# Power.net
KiCad netlist of a schematic drawn in Altium Designer
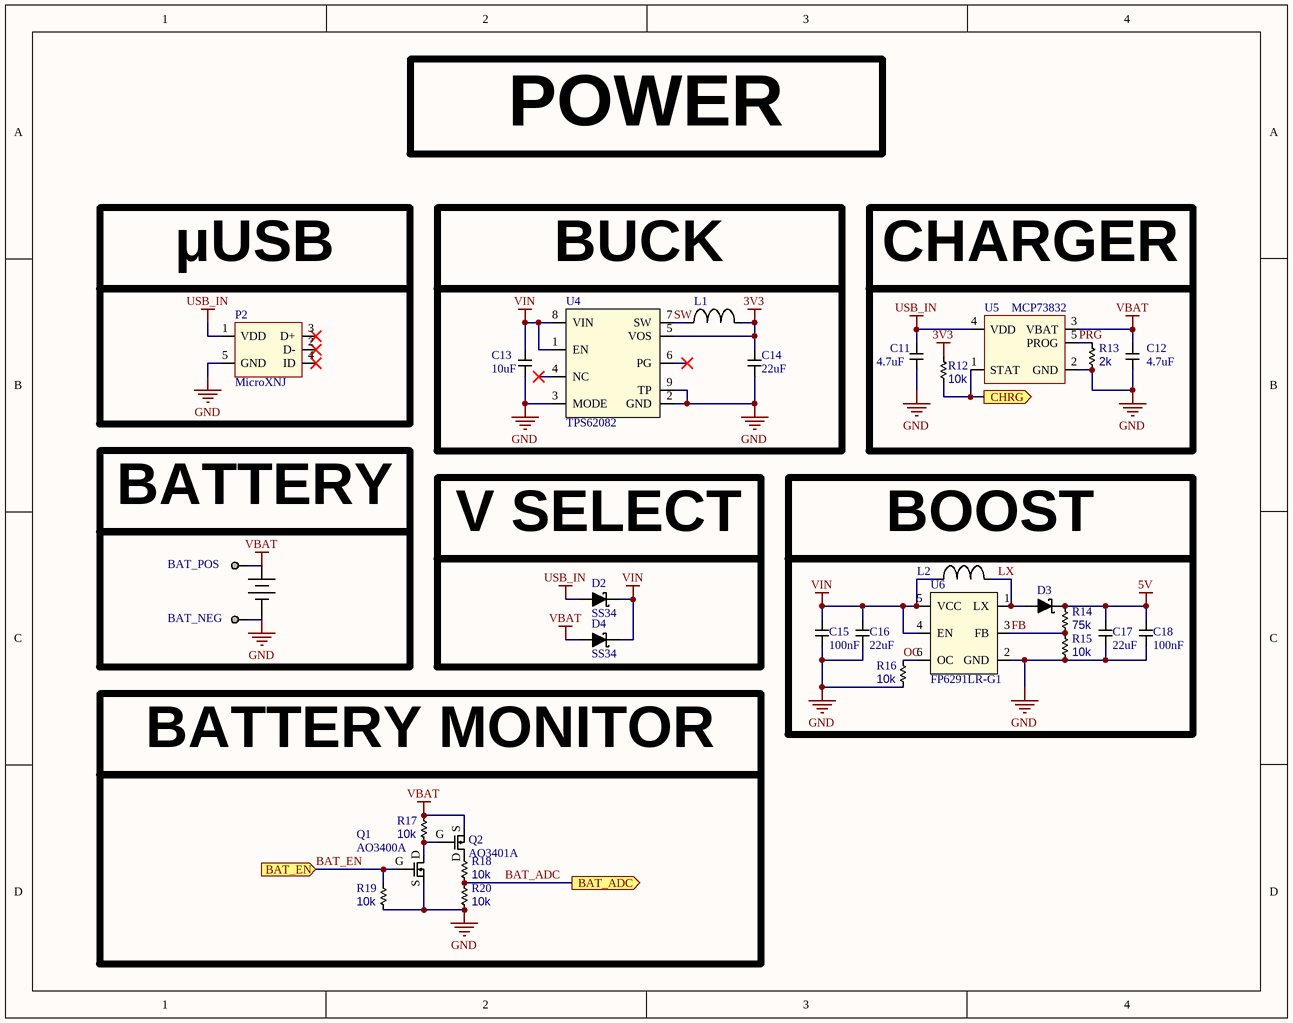
[diagram p0: Power.SchDoc]

(export (version "E")
  (design (tool "Eeschema 10.0.6"))
  (components
    (comp (ref "BAT_NEG")
      (value "18 AWG Hole")
      (footprint "18 AWG Hole")
      (libsource (lib "smLib") (part "18 AWG Hole"))
    )
    (comp (ref "BAT_POS")
      (value "18 AWG Hole")
      (footprint "18 AWG Hole")
      (libsource (lib "smLib") (part "18 AWG Hole"))
    )
    (comp (ref "C11")
      (value "4.7uF")
      (footprint "CAP_0402_HIGH")
      (description "0402 Capacitor")
      (libsource (lib "smLib") (part "Capacitor_0402"))
    )
    (comp (ref "C12")
      (value "4.7uF")
      (footprint "CAP_0402_HIGH")
      (description "0402 Capacitor")
      (libsource (lib "smLib") (part "Capacitor_0402"))
    )
    (comp (ref "C13")
      (value "10uF")
      (footprint "CAP_0603_HIGH")
      (description "0603 Capacitor")
      (libsource (lib "smLib") (part "Capacitor_0603"))
    )
    (comp (ref "C14")
      (value "22uF")
      (footprint "CAP_0603_HIGH")
      (description "0603 Capacitor")
      (libsource (lib "smLib") (part "Capacitor_0603"))
    )
    (comp (ref "C15")
      (value "100nF")
      (footprint "CAP_0402_HIGH")
      (description "0402 Capacitor")
      (libsource (lib "smLib") (part "Capacitor_0402"))
    )
    (comp (ref "C16")
      (value "22uF")
      (footprint "CAP_0603_HIGH")
      (description "0603 Capacitor")
      (libsource (lib "smLib") (part "Capacitor_0603"))
    )
    (comp (ref "C17")
      (value "22uF")
      (footprint "CAP_0603_HIGH")
      (description "0603 Capacitor")
      (libsource (lib "smLib") (part "Capacitor_0603"))
    )
    (comp (ref "C18")
      (value "100nF")
      (footprint "CAP_0402_HIGH")
      (description "0402 Capacitor")
      (libsource (lib "smLib") (part "Capacitor_0402"))
    )
    (comp (ref "D2")
      (value "SS34")
      (footprint "SS34")
      (description "SS34 40V 3A 550mV @ 3A SMA(DO-214AC) Schottky Barrier Diodes (SBD) ROHS")
      (libsource (lib "smLib") (part "SS34"))
    )
    (comp (ref "D3")
      (value "SS34")
      (footprint "SS34")
      (description "SS34 40V 3A 550mV @ 3A SMA(DO-214AC) Schottky Barrier Diodes (SBD) ROHS")
      (libsource (lib "smLib") (part "SS34"))
    )
    (comp (ref "D4")
      (value "SS34")
      (footprint "SS34")
      (description "SS34 40V 3A 550mV @ 3A SMA(DO-214AC) Schottky Barrier Diodes (SBD) ROHS")
      (libsource (lib "smLib") (part "SS34"))
    )
    (comp (ref "L1")
      (value "YNR3015-2R2M")
      (footprint "YNR3015-2R2M")
      (description "YNR3015-2R2M 2.2uH ±20% 1.6A 30mΩ SMD,3.0x3.0x1.5mm Power Inductors RoHS")
      (libsource (lib "smLib") (part "YNR3015-2R2M"))
    )
    (comp (ref "L2")
      (value "VLS3015ET-3R3M")
      (footprint "VLS3015ET-3R3M")
      (description "VLS3015ET-3R3M 3.3 µH Shielded Wirewound Inductor 1.15 A 112mOhm Max Nonstandard")
      (libsource (lib "smLib") (part "VLS3015ET-3R3M"))
    )
    (comp (ref "P2") (value "MicroXNJ") (footprint "MicroXNJ") (libsource (lib "smLib") (part "MicroXNJ")))
    (comp (ref "Q1")
      (value "AO3400A")
      (footprint "AO3400A")
      (description "AO3400A N-Channel 30 V 5.7A (Ta) 1.4W (Ta) Surface Mount SOT-23-3")
      (libsource (lib "smLib") (part "AO3400A"))
    )
    (comp (ref "Q2")
      (value "AO3401A")
      (footprint "AO3401A")
      (description "AO3401A MOSFET P-CH 30V 4A SOT23")
      (libsource (lib "smLib") (part "AO3401A"))
    )
    (comp (ref "R12")
      (value "10k")
      (footprint "RES_0402_HIGH")
      (description "0402 Resistor")
      (libsource (lib "smLib") (part "Resistor_0402"))
    )
    (comp (ref "R13")
      (value "2k")
      (footprint "RES_0402_HIGH")
      (description "0402 Resistor")
      (libsource (lib "smLib") (part "Resistor_0402"))
    )
    (comp (ref "R14")
      (value "75k")
      (footprint "RES_0402_HIGH")
      (description "0402 Resistor")
      (libsource (lib "smLib") (part "Resistor_0402"))
    )
    (comp (ref "R15")
      (value "10k")
      (footprint "RES_0402_HIGH")
      (description "0402 Resistor")
      (libsource (lib "smLib") (part "Resistor_0402"))
    )
    (comp (ref "R16")
      (value "10k")
      (footprint "RES_0402_HIGH")
      (description "0402 Resistor")
      (libsource (lib "smLib") (part "Resistor_0402"))
    )
    (comp (ref "R17")
      (value "10k")
      (footprint "RES_0402_HIGH")
      (description "0402 Resistor")
      (libsource (lib "smLib") (part "Resistor_0402"))
    )
    (comp (ref "R18")
      (value "10k")
      (footprint "RES_0402_HIGH")
      (description "0402 Resistor")
      (libsource (lib "smLib") (part "Resistor_0402"))
    )
    (comp (ref "R19")
      (value "10k")
      (footprint "RES_0402_HIGH")
      (description "0402 Resistor")
      (libsource (lib "smLib") (part "Resistor_0402"))
    )
    (comp (ref "R20")
      (value "10k")
      (footprint "RES_0402_HIGH")
      (description "0402 Resistor")
      (libsource (lib "smLib") (part "Resistor_0402"))
    )
    (comp (ref "U4")
      (value "TPS62082")
      (footprint "TPS62082")
      (description "TPS62082 Buck Switching Regulator IC Positive Fixed 3.3V 1 Output 1.2A 8-WFDFN Exposed Pad")
      (libsource (lib "smLib") (part "TPS62082"))
    )
    (comp (ref "U5")
      (value "MCP73832")
      (footprint "MCP73831")
      (description "MCP73831 Charger IC Lithium-Ion/Polymer")
      (libsource (lib "smLib") (part "MCP73831"))
    )
    (comp (ref "U6")
      (value "FP6291LR-G1")
      (footprint "FP6291LR-G1")
      (description "FP6291LR-G1 2A 5.5V SOT-23-6 DC-DC Converters ROHS")
      (libsource (lib "smLib") (part "FP6291LR-G1"))
    )
  )
  (nets
    (net (code "1") (name "/BAT_ADC") (class "Default")
      (node (ref "R18") (pin "2") (pinfunction "2_2") (pintype "passive"))
      (node (ref "R20") (pin "1") (pinfunction "1_1") (pintype "passive"))
    )
    (net (code "2") (name "/BAT_EN") (class "Default")
      (node (ref "Q1") (pin "G") (pinfunction "G_G") (pintype "passive"))
      (node (ref "R19") (pin "1") (pinfunction "1_1") (pintype "passive"))
    )
    (net (code "3") (name "/CHRG") (class "Default")
      (node (ref "R12") (pin "2") (pinfunction "2_2") (pintype "passive"))
      (node (ref "U5") (pin "1") (pinfunction "STAT_1") (pintype "passive"))
    )
    (net (code "4") (name "/FB") (class "Default")
      (node (ref "R14") (pin "2") (pinfunction "2_2") (pintype "passive"))
      (node (ref "R15") (pin "1") (pinfunction "1_1") (pintype "passive"))
      (node (ref "U6") (pin "3") (pinfunction "FB_3") (pintype "passive"))
    )
    (net (code "5") (name "/LX") (class "Default")
      (node (ref "D3") (pin "1") (pinfunction "1_1") (pintype "passive"))
      (node (ref "L2") (pin "2") (pinfunction "2_2") (pintype "passive"))
      (node (ref "U6") (pin "1") (pinfunction "LX_1") (pintype "passive"))
    )
    (net (code "6") (name "/OC") (class "Default")
      (node (ref "R16") (pin "1") (pinfunction "1_1") (pintype "passive"))
      (node (ref "U6") (pin "6") (pinfunction "OC_6") (pintype "passive"))
    )
    (net (code "7") (name "/PRG") (class "Default")
      (node (ref "R13") (pin "1") (pinfunction "1_1") (pintype "passive"))
      (node (ref "U5") (pin "5") (pinfunction "PROG_5") (pintype "passive"))
    )
    (net (code "8") (name "/SW") (class "Default")
      (node (ref "L1") (pin "1") (pinfunction "1_1") (pintype "passive"))
      (node (ref "U4") (pin "7") (pinfunction "SW_7") (pintype "passive"))
    )
    (net (code "9") (name "3V3") (class "Default")
      (node (ref "C14") (pin "2") (pinfunction "2_2") (pintype "passive"))
      (node (ref "L1") (pin "2") (pinfunction "2_2") (pintype "passive"))
      (node (ref "R12") (pin "1") (pinfunction "1_1") (pintype "passive"))
      (node (ref "U4") (pin "5") (pinfunction "VOS_5") (pintype "passive"))
    )
    (net (code "10") (name "5V") (class "Default")
      (node (ref "C17") (pin "2") (pinfunction "2_2") (pintype "passive"))
      (node (ref "C18") (pin "2") (pinfunction "2_2") (pintype "passive"))
      (node (ref "D3") (pin "2") (pinfunction "2_2") (pintype "passive"))
      (node (ref "R14") (pin "1") (pinfunction "1_1") (pintype "passive"))
    )
    (net (code "11") (name "GND") (class "Default")
      (node (ref "BAT_NEG") (pin "1") (pinfunction "1_1") (pintype "passive"))
      (node (ref "C11") (pin "1") (pinfunction "1_1") (pintype "passive"))
      (node (ref "C12") (pin "1") (pinfunction "1_1") (pintype "passive"))
      (node (ref "C13") (pin "1") (pinfunction "1_1") (pintype "passive"))
      (node (ref "C14") (pin "1") (pinfunction "1_1") (pintype "passive"))
      (node (ref "C15") (pin "1") (pinfunction "1_1") (pintype "passive"))
      (node (ref "C16") (pin "1") (pinfunction "1_1") (pintype "passive"))
      (node (ref "C17") (pin "1") (pinfunction "1_1") (pintype "passive"))
      (node (ref "C18") (pin "1") (pinfunction "1_1") (pintype "passive"))
      (node (ref "P2") (pin "5") (pinfunction "GND_5") (pintype "passive"))
      (node (ref "Q1") (pin "S") (pinfunction "S_S") (pintype "passive"))
      (node (ref "R13") (pin "2") (pinfunction "2_2") (pintype "passive"))
      (node (ref "R15") (pin "2") (pinfunction "2_2") (pintype "passive"))
      (node (ref "R16") (pin "2") (pinfunction "2_2") (pintype "passive"))
      (node (ref "R19") (pin "2") (pinfunction "2_2") (pintype "passive"))
      (node (ref "R20") (pin "2") (pinfunction "2_2") (pintype "passive"))
      (node (ref "U4") (pin "2") (pinfunction "GND_2") (pintype "passive"))
      (node (ref "U4") (pin "3") (pinfunction "MODE_3") (pintype "passive"))
      (node (ref "U4") (pin "9") (pinfunction "TP_9") (pintype "passive"))
      (node (ref "U5") (pin "2") (pinfunction "GND_2") (pintype "passive"))
      (node (ref "U6") (pin "2") (pinfunction "GND_2") (pintype "passive"))
    )
    (net (code "12") (name "Net-(Q1-PadD)") (class "Default")
      (node (ref "Q1") (pin "D") (pinfunction "D_D") (pintype "passive"))
      (node (ref "Q2") (pin "G") (pinfunction "G_G") (pintype "passive"))
      (node (ref "R17") (pin "2") (pinfunction "2_2") (pintype "passive"))
    )
    (net (code "13") (name "Net-(Q2-PadD)") (class "Default")
      (node (ref "Q2") (pin "D") (pinfunction "D_D") (pintype "passive"))
      (node (ref "R18") (pin "1") (pinfunction "1_1") (pintype "passive"))
    )
    (net (code "14") (name "USB_IN") (class "Default")
      (node (ref "C11") (pin "2") (pinfunction "2_2") (pintype "passive"))
      (node (ref "D2") (pin "1") (pinfunction "1_1") (pintype "passive"))
      (node (ref "P2") (pin "1") (pinfunction "VDD_1") (pintype "passive"))
      (node (ref "U5") (pin "4") (pinfunction "VDD_4") (pintype "passive"))
    )
    (net (code "15") (name "VBAT") (class "Default")
      (node (ref "BAT_POS") (pin "1") (pinfunction "1_1") (pintype "passive"))
      (node (ref "C12") (pin "2") (pinfunction "2_2") (pintype "passive"))
      (node (ref "D4") (pin "1") (pinfunction "1_1") (pintype "passive"))
      (node (ref "Q2") (pin "S") (pinfunction "S_S") (pintype "passive"))
      (node (ref "R17") (pin "1") (pinfunction "1_1") (pintype "passive"))
      (node (ref "U5") (pin "3") (pinfunction "VBAT_3") (pintype "passive"))
    )
    (net (code "16") (name "VIN") (class "Default")
      (node (ref "C13") (pin "2") (pinfunction "2_2") (pintype "passive"))
      (node (ref "C15") (pin "2") (pinfunction "2_2") (pintype "passive"))
      (node (ref "C16") (pin "2") (pinfunction "2_2") (pintype "passive"))
      (node (ref "D2") (pin "2") (pinfunction "2_2") (pintype "passive"))
      (node (ref "D4") (pin "2") (pinfunction "2_2") (pintype "passive"))
      (node (ref "L2") (pin "1") (pinfunction "1_1") (pintype "passive"))
      (node (ref "U4") (pin "1") (pinfunction "EN_1") (pintype "passive"))
      (node (ref "U4") (pin "8") (pinfunction "VIN_8") (pintype "passive"))
      (node (ref "U6") (pin "4") (pinfunction "EN_4") (pintype "passive"))
      (node (ref "U6") (pin "5") (pinfunction "VCC_5") (pintype "passive"))
    )
    (net (code "17") (name "unconnected-(P2-D+-Pad3)") (class "Default")
      (node (ref "P2") (pin "3") (pinfunction "D+_3") (pintype "passive+no_connect"))
    )
    (net (code "18") (name "unconnected-(P2-D--Pad2)") (class "Default")
      (node (ref "P2") (pin "2") (pinfunction "D-_2") (pintype "passive+no_connect"))
    )
    (net (code "19") (name "unconnected-(P2-ID-Pad4)") (class "Default")
      (node (ref "P2") (pin "4") (pinfunction "ID_4") (pintype "passive+no_connect"))
    )
    (net (code "20") (name "unconnected-(U4-NC-Pad4)") (class "Default")
      (node (ref "U4") (pin "4") (pinfunction "NC_4") (pintype "passive+no_connect"))
    )
    (net (code "21") (name "unconnected-(U4-PG-Pad6)") (class "Default")
      (node (ref "U4") (pin "6") (pinfunction "PG_6") (pintype "passive+no_connect"))
    )
  )
)
